# STM32H730_PINOUT.net
KiCad netlist of a schematic drawn in Altium Designer
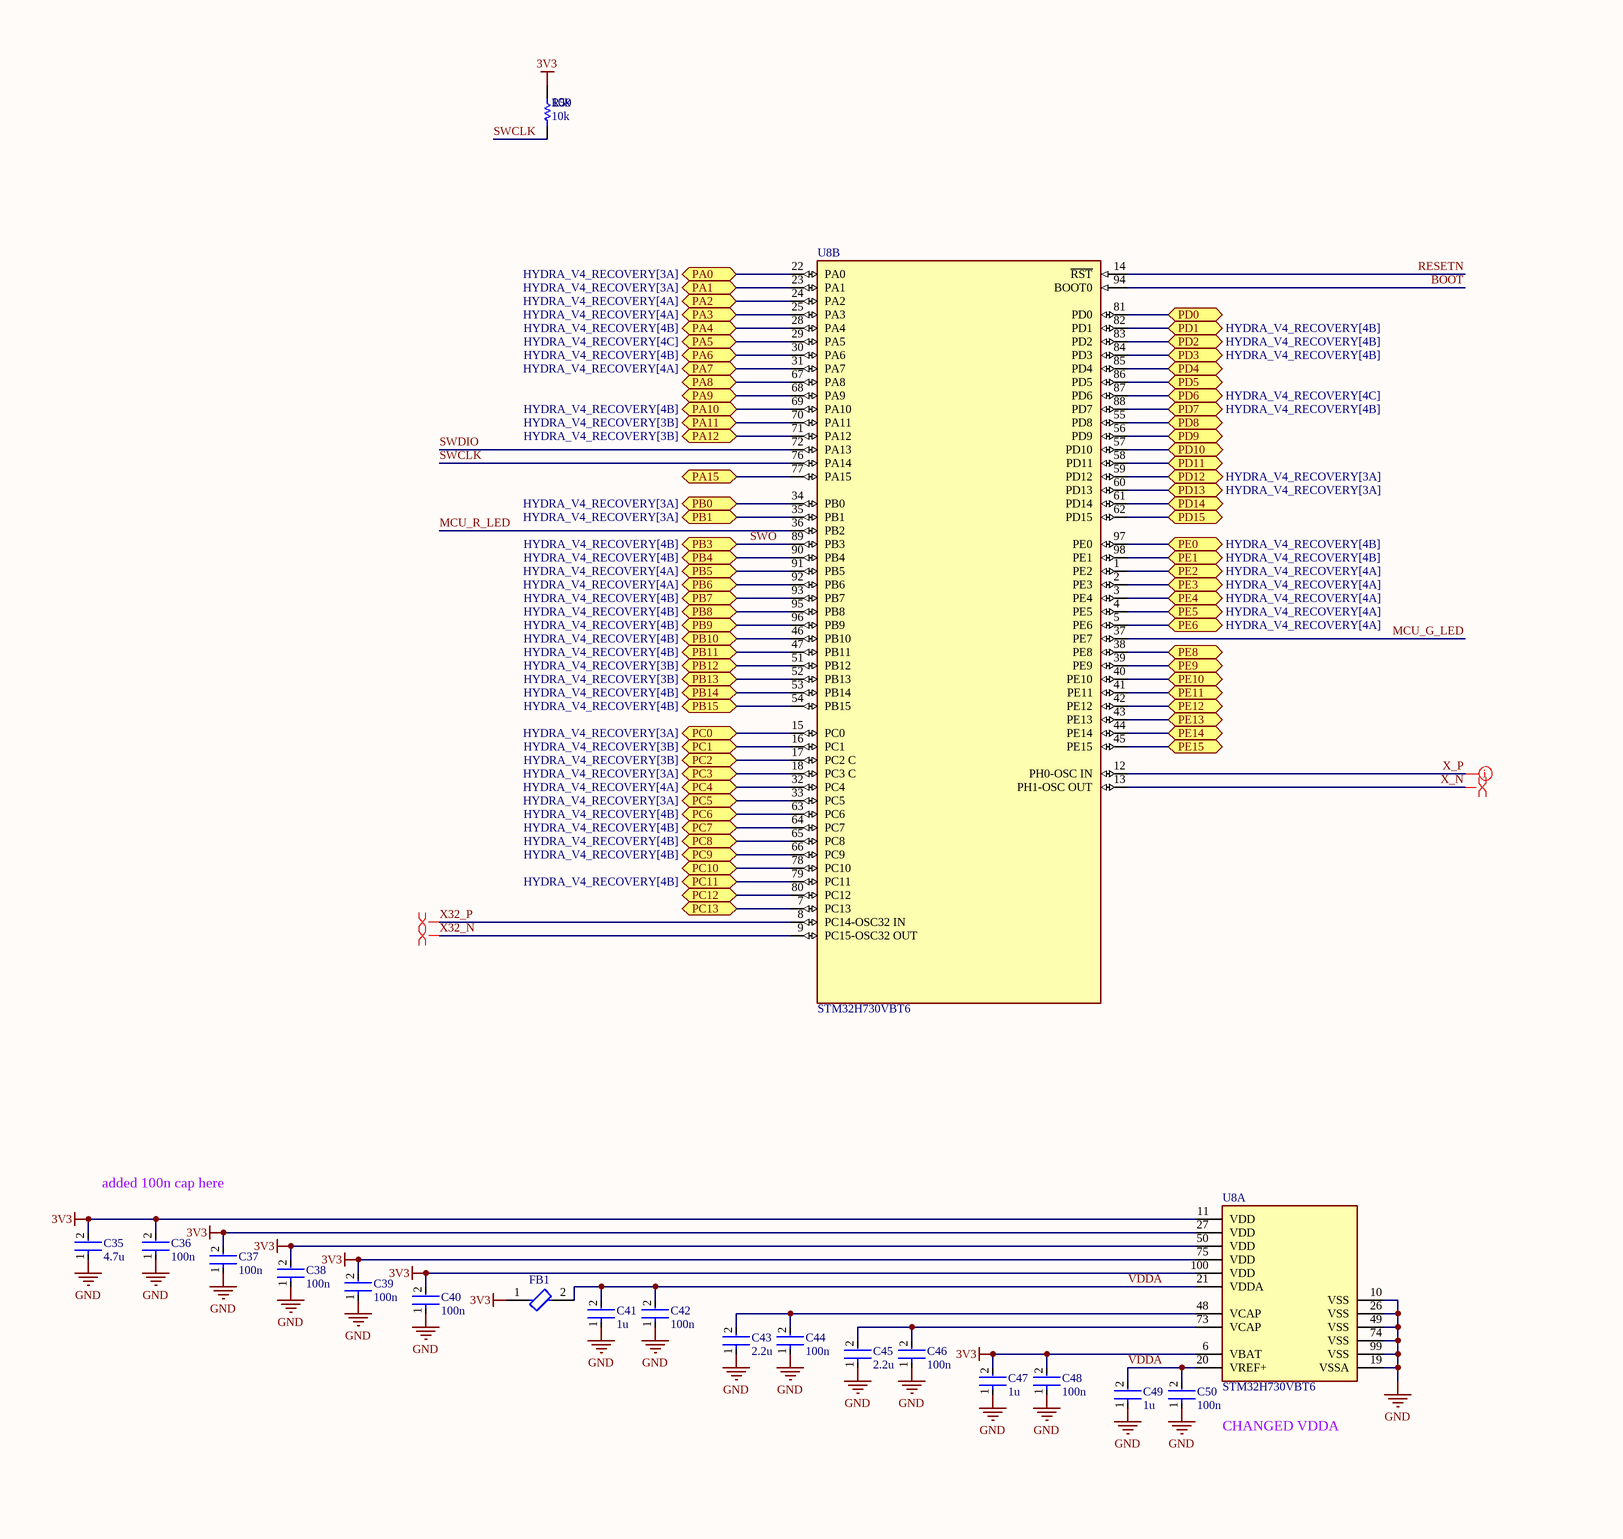
[diagram p0: STM32H730_PINOUT.SchDoc, left]
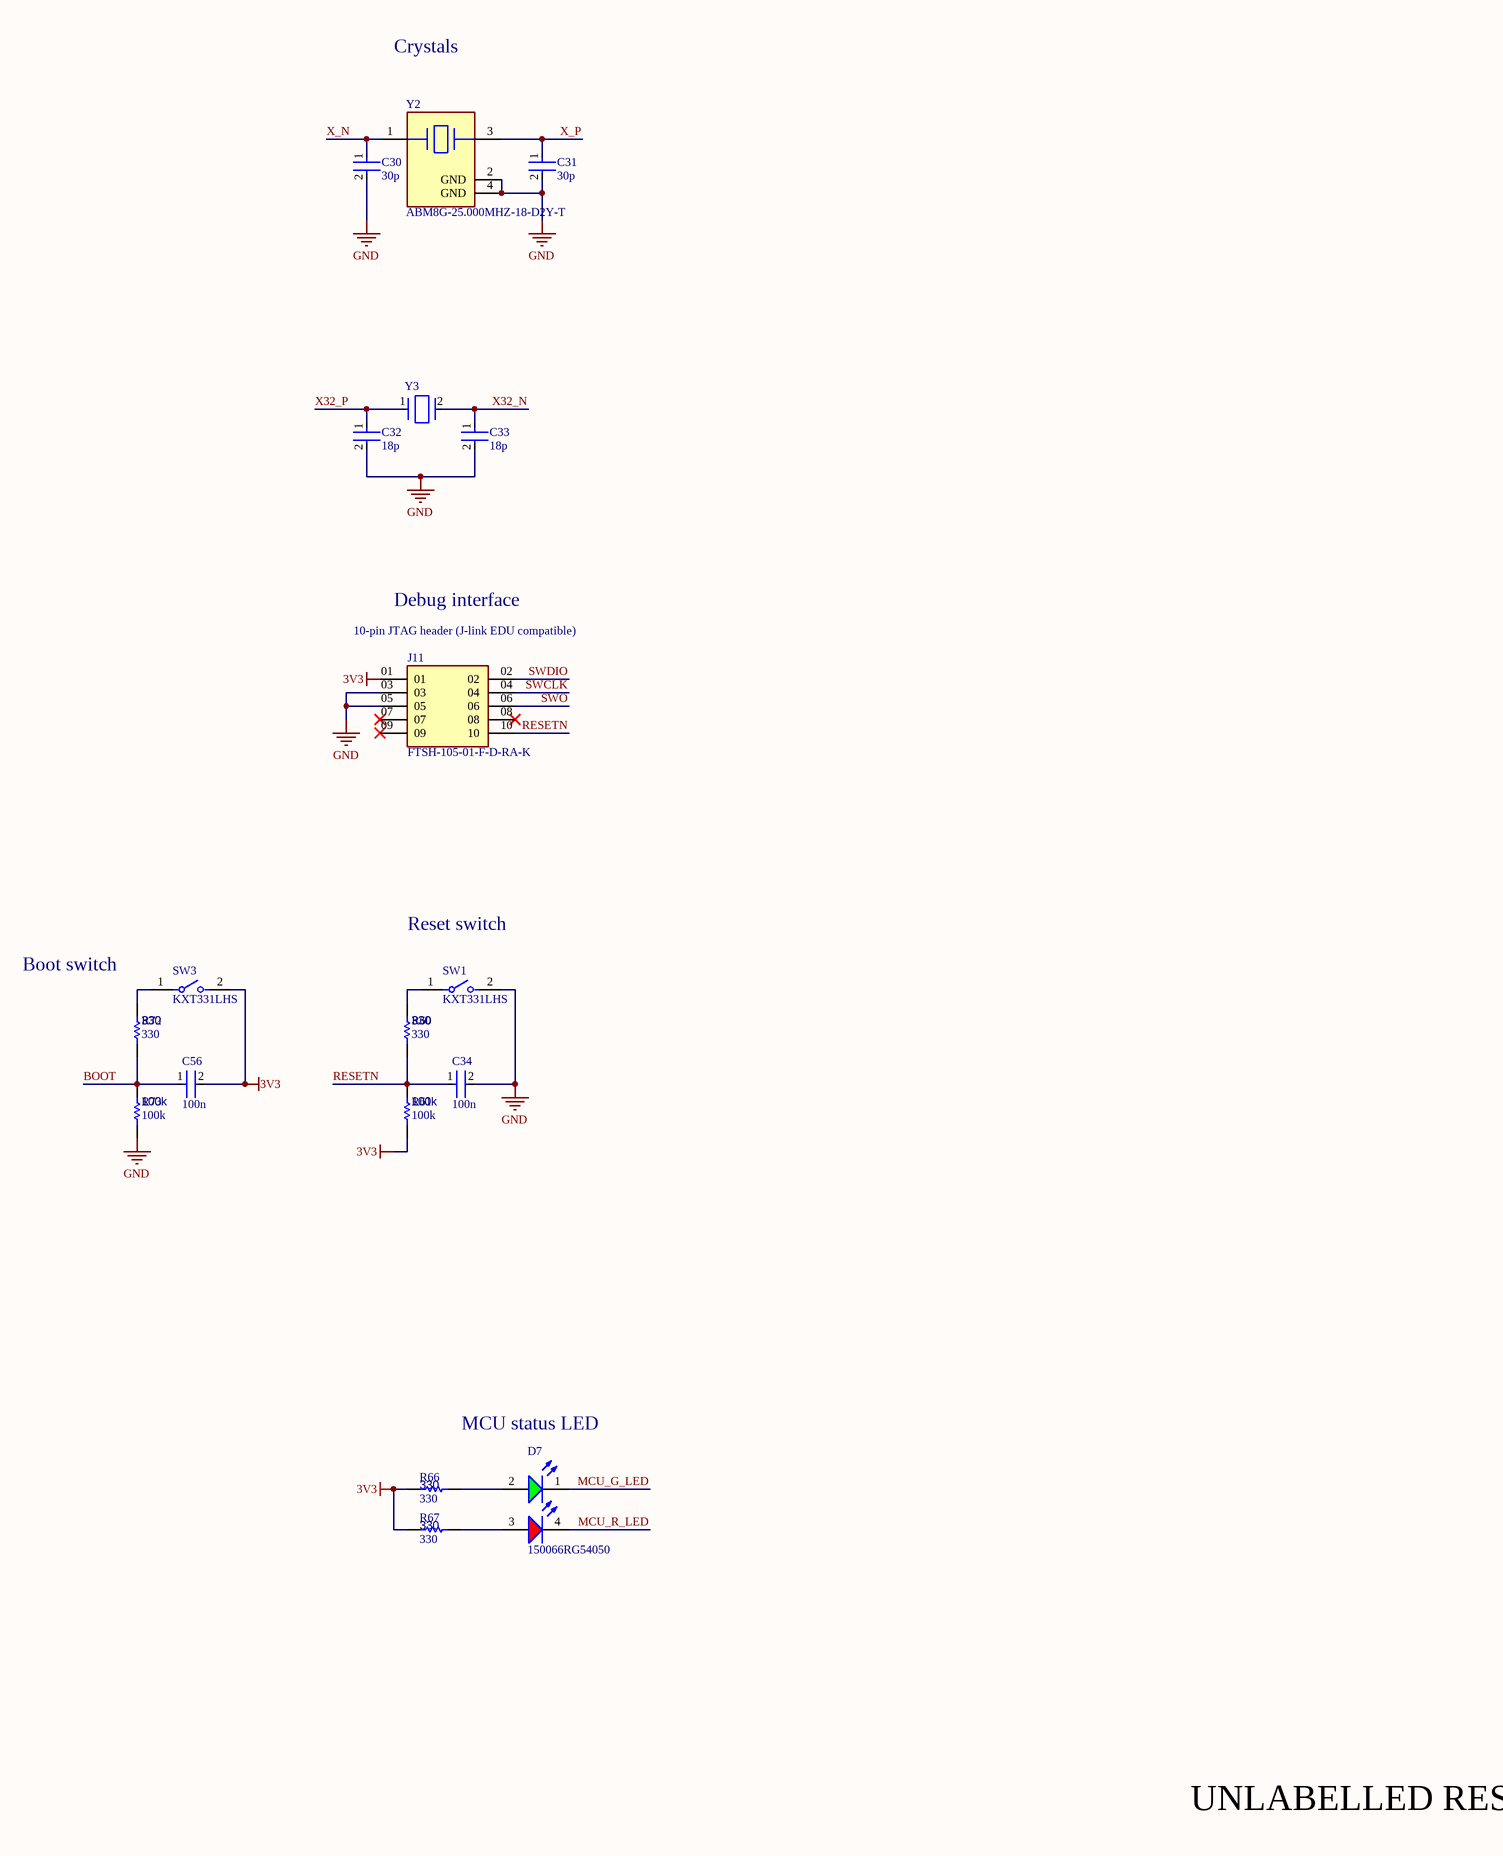
[diagram p1: STM32H730_PINOUT.SchDoc, right]

(export (version "E")
  (design (tool "Eeschema 10.0.6"))
  (components
    (comp (ref "C30")
      (value "30p")
      (footprint "FP-0402-L_1_0_0_05-W_0_5-IPC_A")
      (description "LARGE PADS, 0402 CAP, CHANGE COMMENT TO MATCH REAL P/N")
      (libsource (lib "Space Concordia") (part "b4654b650e69147ec39a6b967a45e02"))
    )
    (comp (ref "C31")
      (value "30p")
      (footprint "FP-0402-L_1_0_0_05-W_0_5-IPC_A")
      (description "LARGE PADS, 0402 CAP, CHANGE COMMENT TO MATCH REAL P/N")
      (libsource (lib "Space Concordia") (part "b4654b650e69147ec39a6b967a45e02"))
    )
    (comp (ref "C32")
      (value "18p")
      (footprint "FP-0402-L_1_0_0_05-W_0_5-IPC_A")
      (description "LARGE PADS, 0402 CAP, CHANGE COMMENT TO MATCH REAL P/N")
      (libsource (lib "Space Concordia") (part "b4654b650e69147ec39a6b967a45e02"))
    )
    (comp (ref "C33")
      (value "18p")
      (footprint "FP-0402-L_1_0_0_05-W_0_5-IPC_A")
      (description "LARGE PADS, 0402 CAP, CHANGE COMMENT TO MATCH REAL P/N")
      (libsource (lib "Space Concordia") (part "b4654b650e69147ec39a6b967a45e02"))
    )
    (comp (ref "C34")
      (value "100n")
      (footprint "FP-0402-L_1_0_0_05-W_0_5-IPC_A")
      (description "LARGE PADS, 0402 CAP, CHANGE COMMENT TO MATCH REAL P/N")
      (libsource (lib "Space Concordia") (part "b4654b650e69147ec39a6b967a45e02"))
    )
    (comp (ref "C35")
      (value "4.7u")
      (footprint "FP-0402-L_1_0_0_05-W_0_5-IPC_A")
      (description "LARGE PADS, 0402 CAP, CHANGE COMMENT TO MATCH REAL P/N")
      (libsource (lib "Space Concordia") (part "b4654b650e69147ec39a6b967a45e02"))
    )
    (comp (ref "C36")
      (value "100n")
      (footprint "FP-0402-L_1_0_0_05-W_0_5-IPC_A")
      (description "LARGE PADS, 0402 CAP, CHANGE COMMENT TO MATCH REAL P/N")
      (libsource (lib "Space Concordia") (part "b4654b650e69147ec39a6b967a45e02"))
    )
    (comp (ref "C37")
      (value "100n")
      (footprint "FP-0402-L_1_0_0_05-W_0_5-IPC_A")
      (description "LARGE PADS, 0402 CAP, CHANGE COMMENT TO MATCH REAL P/N")
      (libsource (lib "Space Concordia") (part "b4654b650e69147ec39a6b967a45e02"))
    )
    (comp (ref "C38")
      (value "100n")
      (footprint "FP-0402-L_1_0_0_05-W_0_5-IPC_A")
      (description "LARGE PADS, 0402 CAP, CHANGE COMMENT TO MATCH REAL P/N")
      (libsource (lib "Space Concordia") (part "b4654b650e69147ec39a6b967a45e02"))
    )
    (comp (ref "C39")
      (value "100n")
      (footprint "FP-0402-L_1_0_0_05-W_0_5-IPC_A")
      (description "LARGE PADS, 0402 CAP, CHANGE COMMENT TO MATCH REAL P/N")
      (libsource (lib "Space Concordia") (part "b4654b650e69147ec39a6b967a45e02"))
    )
    (comp (ref "C40")
      (value "100n")
      (footprint "FP-0402-L_1_0_0_05-W_0_5-IPC_A")
      (description "LARGE PADS, 0402 CAP, CHANGE COMMENT TO MATCH REAL P/N")
      (libsource (lib "Space Concordia") (part "b4654b650e69147ec39a6b967a45e02"))
    )
    (comp (ref "C41")
      (value "1u")
      (footprint "FP-0402-L_1_0_0_05-W_0_5-IPC_A")
      (description "LARGE PADS, 0402 CAP, CHANGE COMMENT TO MATCH REAL P/N")
      (libsource (lib "Space Concordia") (part "b4654b650e69147ec39a6b967a45e02"))
    )
    (comp (ref "C42")
      (value "100n")
      (footprint "FP-0402-L_1_0_0_05-W_0_5-IPC_A")
      (description "LARGE PADS, 0402 CAP, CHANGE COMMENT TO MATCH REAL P/N")
      (libsource (lib "Space Concordia") (part "b4654b650e69147ec39a6b967a45e02"))
    )
    (comp (ref "C43")
      (value "2.2u")
      (footprint "FP-0402-L_1_0_0_05-W_0_5-IPC_A")
      (description "LARGE PADS, 0402 CAP, CHANGE COMMENT TO MATCH REAL P/N")
      (libsource (lib "Space Concordia") (part "b4654b650e69147ec39a6b967a45e02"))
    )
    (comp (ref "C44")
      (value "100n")
      (footprint "FP-0402-L_1_0_0_05-W_0_5-IPC_A")
      (description "LARGE PADS, 0402 CAP, CHANGE COMMENT TO MATCH REAL P/N")
      (libsource (lib "Space Concordia") (part "b4654b650e69147ec39a6b967a45e02"))
    )
    (comp (ref "C45")
      (value "2.2u")
      (footprint "FP-0402-L_1_0_0_05-W_0_5-IPC_A")
      (description "LARGE PADS, 0402 CAP, CHANGE COMMENT TO MATCH REAL P/N")
      (libsource (lib "Space Concordia") (part "b4654b650e69147ec39a6b967a45e02"))
    )
    (comp (ref "C46")
      (value "100n")
      (footprint "FP-0402-L_1_0_0_05-W_0_5-IPC_A")
      (description "LARGE PADS, 0402 CAP, CHANGE COMMENT TO MATCH REAL P/N")
      (libsource (lib "Space Concordia") (part "b4654b650e69147ec39a6b967a45e02"))
    )
    (comp (ref "C47")
      (value "1u")
      (footprint "FP-0402-L_1_0_0_05-W_0_5-IPC_A")
      (description "LARGE PADS, 0402 CAP, CHANGE COMMENT TO MATCH REAL P/N")
      (libsource (lib "Space Concordia") (part "b4654b650e69147ec39a6b967a45e02"))
    )
    (comp (ref "C48")
      (value "100n")
      (footprint "FP-0402-L_1_0_0_05-W_0_5-IPC_A")
      (description "LARGE PADS, 0402 CAP, CHANGE COMMENT TO MATCH REAL P/N")
      (libsource (lib "Space Concordia") (part "b4654b650e69147ec39a6b967a45e02"))
    )
    (comp (ref "C49")
      (value "1u")
      (footprint "FP-0402-L_1_0_0_05-W_0_5-IPC_A")
      (description "LARGE PADS, 0402 CAP, CHANGE COMMENT TO MATCH REAL P/N")
      (libsource (lib "Space Concordia") (part "b4654b650e69147ec39a6b967a45e02"))
    )
    (comp (ref "C50")
      (value "100n")
      (footprint "FP-0402-L_1_0_0_05-W_0_5-IPC_A")
      (description "LARGE PADS, 0402 CAP, CHANGE COMMENT TO MATCH REAL P/N")
      (libsource (lib "Space Concordia") (part "b4654b650e69147ec39a6b967a45e02"))
    )
    (comp (ref "C56")
      (value "100n")
      (footprint "FP-0402-L_1_0_0_05-W_0_5-IPC_A")
      (description "LARGE PADS, 0402 CAP, CHANGE COMMENT TO MATCH REAL P/N")
      (libsource (lib "Space Concordia") (part "b4654b650e69147ec39a6b967a45e02"))
    )
    (comp (ref "D7")
      (value "150066RG54050")
      (footprint "WL-SBCD_0606")
      (description "Led, Red/Grn, 180Mcd/230Mcd, 624Nm/525Nm Rohs Compliant: Yes")
      (fields (field (name "SOURCE") "rgled.SchLib"))
      (libsource (lib "Space Concordia") (part "CMP-004-00034-2"))
    )
    (comp (ref "FB1")
      (value "BLM15PX601SN1D")
      (footprint "FP-BLM15-0_05-MFG")
      (description "Chip Ferrite Bead, 0402, 600Ω @ 100MHz, 0.23Ω, 25%, 900mA")
      (fields (field (name "TOLERANCE") "25%"))
      (libsource (lib "Altium Content Vault") (part "5f30dd21d616792df468990f7003faa"))
    )
    (comp (ref "J11")
      (value "FTSH-105-01-F-D-RA-K")
      (footprint "FTSH-105-01-F-D-RA-K-Footprint-1")
      (libsource (lib "Space Concordia") (part "FTSH-105-01-F-D-RA-K-Symbol-1"))
    )
    (comp (ref "R59")
      (value "10k")
      (footprint "R0603B")
      (description "Resistor")
      (fields (field (name "ALTIUM_VALUE") "10k"))
      (libsource (lib "Space Concordia") (part "Resistor"))
    )
    (comp (ref "R60")
      (value "330")
      (footprint "R0603B")
      (description "Resistor")
      (fields (field (name "ALTIUM_VALUE") "330"))
      (libsource (lib "Space Concordia") (part "Resistor"))
    )
    (comp (ref "R61")
      (value "100k")
      (footprint "R0603B")
      (description "Resistor")
      (fields (field (name "ALTIUM_VALUE") "100k"))
      (libsource (lib "Space Concordia") (part "Resistor"))
    )
    (comp (ref "R66")
      (value "330")
      (footprint "R0603B")
      (description "Resistor")
      (fields (field (name "ALTIUM_VALUE") "330"))
      (libsource (lib "Space Concordia") (part "Resistor"))
    )
    (comp (ref "R67")
      (value "330")
      (footprint "R0603B")
      (description "Resistor")
      (fields (field (name "ALTIUM_VALUE") "330"))
      (libsource (lib "Space Concordia") (part "Resistor"))
    )
    (comp (ref "R72")
      (value "330")
      (footprint "R0603B")
      (description "Resistor")
      (fields (field (name "ALTIUM_VALUE") "330"))
      (libsource (lib "Space Concordia") (part "Resistor"))
    )
    (comp (ref "R73")
      (value "100k")
      (footprint "R0603B")
      (description "Resistor")
      (fields (field (name "ALTIUM_VALUE") "100k"))
      (libsource (lib "Space Concordia") (part "Resistor"))
    )
    (comp (ref "SW1")
      (value "KXT331LHS")
      (footprint "FP-KXT331LHS-MFG")
      (description "SWITCH TACTILE SPST-NO 0.02A 15V")
      (libsource (lib "Altium Content Vault") (part "bb27bde45df87f1f469753f287ef5ae"))
    )
    (comp (ref "SW3")
      (value "KXT331LHS")
      (footprint "FP-KXT331LHS-MFG")
      (description "SWITCH TACTILE SPST-NO 0.02A 15V")
      (libsource (lib "Altium Content Vault") (part "bb27bde45df87f1f469753f287ef5ae"))
    )
    (comp (ref "U8")
      (value "STM32H730VBT6")
      (footprint "FP-LQFP100-1L-IPC_C")
      (description "IC MCU 32BIT 128KB FLASH 100LQFP")
      (libsource (lib "Altium Content Vault") (part "44dc6501260a4d92b846760feb66c20"))
    )
    (comp (ref "Y2")
      (value "ABM8G-25.000MHZ-18-D2Y-T")
      (footprint "FP-ABM8G-MFG")
      (description "Crystal 25MHz ±20ppm (Tol) ±30ppm (Stability) 18pF FUND 60Ω 4-Pin SMD T/R")
      (fields (field (name "TOLERANCE") "20ppm"))
      (libsource (lib "Altium Content Vault") (part "48e526d86b7f2615d98721063c72f49"))
    )
    (comp (ref "Y3")
      (value "ECS-.327-12.5-1210-TR")
      (footprint "FP-ECX-1210-MFG")
      (description "CRYSTAL 32.7680KHZ 12.5PF SMD")
      (fields
        (field (name "OCTOPART") "https://octopart.com/ecs-.327-12.5-1210-tr-ecs+international-81221340")
        (field (name "TOLERANCE") "20ppm")
      )
      (libsource (lib "Altium Content Vault") (part "99724985039315a44fd0d1401b84e49"))
    )
  )
  (nets
    (net (code "1") (name "/BOOT") (class "Default")
      (node (ref "C56") (pin "1") (pinfunction "1_1") (pintype "passive"))
      (node (ref "R72") (pin "2") (pinfunction "2_2") (pintype "passive"))
      (node (ref "R73") (pin "2") (pinfunction "2_2") (pintype "passive"))
      (node (ref "U8") (pin "94") (pinfunction "BOOT0_94") (pintype "input"))
    )
    (net (code "2") (name "/MCU_G_LED") (class "Default")
      (node (ref "D7") (pin "1") (pinfunction "K_1") (pintype "passive"))
      (node (ref "U8") (pin "37") (pinfunction "PE7_37") (pintype "bidirectional"))
    )
    (net (code "3") (name "/MCU_R_LED") (class "Default")
      (node (ref "D7") (pin "4") (pinfunction "K_4") (pintype "passive"))
      (node (ref "U8") (pin "36") (pinfunction "PB2_36") (pintype "bidirectional"))
    )
    (net (code "4") (name "/PA0") (class "Default")
      (node (ref "U8") (pin "22") (pinfunction "PA0_22") (pintype "bidirectional"))
    )
    (net (code "5") (name "/PA1") (class "Default")
      (node (ref "U8") (pin "23") (pinfunction "PA1_23") (pintype "bidirectional"))
    )
    (net (code "6") (name "/PA2") (class "Default")
      (node (ref "U8") (pin "24") (pinfunction "PA2_24") (pintype "bidirectional"))
    )
    (net (code "7") (name "/PA3") (class "Default")
      (node (ref "U8") (pin "25") (pinfunction "PA3_25") (pintype "bidirectional"))
    )
    (net (code "8") (name "/PA4") (class "Default")
      (node (ref "U8") (pin "28") (pinfunction "PA4_28") (pintype "bidirectional"))
    )
    (net (code "9") (name "/PA5") (class "Default")
      (node (ref "U8") (pin "29") (pinfunction "PA5_29") (pintype "bidirectional"))
    )
    (net (code "10") (name "/PA6") (class "Default")
      (node (ref "U8") (pin "30") (pinfunction "PA6_30") (pintype "bidirectional"))
    )
    (net (code "11") (name "/PA7") (class "Default")
      (node (ref "U8") (pin "31") (pinfunction "PA7_31") (pintype "bidirectional"))
    )
    (net (code "12") (name "/PA8") (class "Default")
      (node (ref "U8") (pin "67") (pinfunction "PA8_67") (pintype "bidirectional"))
    )
    (net (code "13") (name "/PA9") (class "Default")
      (node (ref "U8") (pin "68") (pinfunction "PA9_68") (pintype "bidirectional"))
    )
    (net (code "14") (name "/PA10") (class "Default")
      (node (ref "U8") (pin "69") (pinfunction "PA10_69") (pintype "bidirectional"))
    )
    (net (code "15") (name "/PA11") (class "Default")
      (node (ref "U8") (pin "70") (pinfunction "PA11_70") (pintype "bidirectional"))
    )
    (net (code "16") (name "/PA12") (class "Default")
      (node (ref "U8") (pin "71") (pinfunction "PA12_71") (pintype "bidirectional"))
    )
    (net (code "17") (name "/PA15") (class "Default")
      (node (ref "U8") (pin "77") (pinfunction "PA15_77") (pintype "bidirectional"))
    )
    (net (code "18") (name "/PB0") (class "Default")
      (node (ref "U8") (pin "34") (pinfunction "PB0_34") (pintype "bidirectional"))
    )
    (net (code "19") (name "/PB1") (class "Default")
      (node (ref "U8") (pin "35") (pinfunction "PB1_35") (pintype "bidirectional"))
    )
    (net (code "20") (name "/PB4") (class "Default")
      (node (ref "U8") (pin "90") (pinfunction "PB4_90") (pintype "bidirectional"))
    )
    (net (code "21") (name "/PB5") (class "Default")
      (node (ref "U8") (pin "91") (pinfunction "PB5_91") (pintype "bidirectional"))
    )
    (net (code "22") (name "/PB6") (class "Default")
      (node (ref "U8") (pin "92") (pinfunction "PB6_92") (pintype "bidirectional"))
    )
    (net (code "23") (name "/PB7") (class "Default")
      (node (ref "U8") (pin "93") (pinfunction "PB7_93") (pintype "bidirectional"))
    )
    (net (code "24") (name "/PB8") (class "Default")
      (node (ref "U8") (pin "95") (pinfunction "PB8_95") (pintype "bidirectional"))
    )
    (net (code "25") (name "/PB9") (class "Default")
      (node (ref "U8") (pin "96") (pinfunction "PB9_96") (pintype "bidirectional"))
    )
    (net (code "26") (name "/PB10") (class "Default")
      (node (ref "U8") (pin "46") (pinfunction "PB10_46") (pintype "bidirectional"))
    )
    (net (code "27") (name "/PB11") (class "Default")
      (node (ref "U8") (pin "47") (pinfunction "PB11_47") (pintype "bidirectional"))
    )
    (net (code "28") (name "/PB12") (class "Default")
      (node (ref "U8") (pin "51") (pinfunction "PB12_51") (pintype "bidirectional"))
    )
    (net (code "29") (name "/PB13") (class "Default")
      (node (ref "U8") (pin "52") (pinfunction "PB13_52") (pintype "bidirectional"))
    )
    (net (code "30") (name "/PB14") (class "Default")
      (node (ref "U8") (pin "53") (pinfunction "PB14_53") (pintype "bidirectional"))
    )
    (net (code "31") (name "/PB15") (class "Default")
      (node (ref "U8") (pin "54") (pinfunction "PB15_54") (pintype "bidirectional"))
    )
    (net (code "32") (name "/PC0") (class "Default")
      (node (ref "U8") (pin "15") (pinfunction "PC0_15") (pintype "bidirectional"))
    )
    (net (code "33") (name "/PC1") (class "Default")
      (node (ref "U8") (pin "16") (pinfunction "PC1_16") (pintype "bidirectional"))
    )
    (net (code "34") (name "/PC2") (class "Default")
      (node (ref "U8") (pin "17") (pinfunction "PC2_C_17") (pintype "bidirectional"))
    )
    (net (code "35") (name "/PC3") (class "Default")
      (node (ref "U8") (pin "18") (pinfunction "PC3_C_18") (pintype "bidirectional"))
    )
    (net (code "36") (name "/PC4") (class "Default")
      (node (ref "U8") (pin "32") (pinfunction "PC4_32") (pintype "bidirectional"))
    )
    (net (code "37") (name "/PC5") (class "Default")
      (node (ref "U8") (pin "33") (pinfunction "PC5_33") (pintype "bidirectional"))
    )
    (net (code "38") (name "/PC6") (class "Default")
      (node (ref "U8") (pin "63") (pinfunction "PC6_63") (pintype "bidirectional"))
    )
    (net (code "39") (name "/PC7") (class "Default")
      (node (ref "U8") (pin "64") (pinfunction "PC7_64") (pintype "bidirectional"))
    )
    (net (code "40") (name "/PC8") (class "Default")
      (node (ref "U8") (pin "65") (pinfunction "PC8_65") (pintype "bidirectional"))
    )
    (net (code "41") (name "/PC9") (class "Default")
      (node (ref "U8") (pin "66") (pinfunction "PC9_66") (pintype "bidirectional"))
    )
    (net (code "42") (name "/PC10") (class "Default")
      (node (ref "U8") (pin "78") (pinfunction "PC10_78") (pintype "bidirectional"))
    )
    (net (code "43") (name "/PC11") (class "Default")
      (node (ref "U8") (pin "79") (pinfunction "PC11_79") (pintype "bidirectional"))
    )
    (net (code "44") (name "/PC12") (class "Default")
      (node (ref "U8") (pin "80") (pinfunction "PC12_80") (pintype "bidirectional"))
    )
    (net (code "45") (name "/PC13") (class "Default")
      (node (ref "U8") (pin "7") (pinfunction "PC13_7") (pintype "bidirectional"))
    )
    (net (code "46") (name "/PD0") (class "Default")
      (node (ref "U8") (pin "81") (pinfunction "PD0_81") (pintype "bidirectional"))
    )
    (net (code "47") (name "/PD1") (class "Default")
      (node (ref "U8") (pin "82") (pinfunction "PD1_82") (pintype "bidirectional"))
    )
    (net (code "48") (name "/PD2") (class "Default")
      (node (ref "U8") (pin "83") (pinfunction "PD2_83") (pintype "bidirectional"))
    )
    (net (code "49") (name "/PD3") (class "Default")
      (node (ref "U8") (pin "84") (pinfunction "PD3_84") (pintype "bidirectional"))
    )
    (net (code "50") (name "/PD4") (class "Default")
      (node (ref "U8") (pin "85") (pinfunction "PD4_85") (pintype "bidirectional"))
    )
    (net (code "51") (name "/PD5") (class "Default")
      (node (ref "U8") (pin "86") (pinfunction "PD5_86") (pintype "bidirectional"))
    )
    (net (code "52") (name "/PD6") (class "Default")
      (node (ref "U8") (pin "87") (pinfunction "PD6_87") (pintype "bidirectional"))
    )
    (net (code "53") (name "/PD7") (class "Default")
      (node (ref "U8") (pin "88") (pinfunction "PD7_88") (pintype "bidirectional"))
    )
    (net (code "54") (name "/PD8") (class "Default")
      (node (ref "U8") (pin "55") (pinfunction "PD8_55") (pintype "bidirectional"))
    )
    (net (code "55") (name "/PD9") (class "Default")
      (node (ref "U8") (pin "56") (pinfunction "PD9_56") (pintype "bidirectional"))
    )
    (net (code "56") (name "/PD10") (class "Default")
      (node (ref "U8") (pin "57") (pinfunction "PD10_57") (pintype "bidirectional"))
    )
    (net (code "57") (name "/PD11") (class "Default")
      (node (ref "U8") (pin "58") (pinfunction "PD11_58") (pintype "bidirectional"))
    )
    (net (code "58") (name "/PD12") (class "Default")
      (node (ref "U8") (pin "59") (pinfunction "PD12_59") (pintype "bidirectional"))
    )
    (net (code "59") (name "/PD13") (class "Default")
      (node (ref "U8") (pin "60") (pinfunction "PD13_60") (pintype "bidirectional"))
    )
    (net (code "60") (name "/PD14") (class "Default")
      (node (ref "U8") (pin "61") (pinfunction "PD14_61") (pintype "bidirectional"))
    )
    (net (code "61") (name "/PD15") (class "Default")
      (node (ref "U8") (pin "62") (pinfunction "PD15_62") (pintype "bidirectional"))
    )
    (net (code "62") (name "/PE0") (class "Default")
      (node (ref "U8") (pin "97") (pinfunction "PE0_97") (pintype "bidirectional"))
    )
    (net (code "63") (name "/PE1") (class "Default")
      (node (ref "U8") (pin "98") (pinfunction "PE1_98") (pintype "bidirectional"))
    )
    (net (code "64") (name "/PE2") (class "Default")
      (node (ref "U8") (pin "1") (pinfunction "PE2_1") (pintype "bidirectional"))
    )
    (net (code "65") (name "/PE3") (class "Default")
      (node (ref "U8") (pin "2") (pinfunction "PE3_2") (pintype "bidirectional"))
    )
    (net (code "66") (name "/PE4") (class "Default")
      (node (ref "U8") (pin "3") (pinfunction "PE4_3") (pintype "bidirectional"))
    )
    (net (code "67") (name "/PE5") (class "Default")
      (node (ref "U8") (pin "4") (pinfunction "PE5_4") (pintype "bidirectional"))
    )
    (net (code "68") (name "/PE6") (class "Default")
      (node (ref "U8") (pin "5") (pinfunction "PE6_5") (pintype "bidirectional"))
    )
    (net (code "69") (name "/PE8") (class "Default")
      (node (ref "U8") (pin "38") (pinfunction "PE8_38") (pintype "bidirectional"))
    )
    (net (code "70") (name "/PE9") (class "Default")
      (node (ref "U8") (pin "39") (pinfunction "PE9_39") (pintype "bidirectional"))
    )
    (net (code "71") (name "/PE10") (class "Default")
      (node (ref "U8") (pin "40") (pinfunction "PE10_40") (pintype "bidirectional"))
    )
    (net (code "72") (name "/PE11") (class "Default")
      (node (ref "U8") (pin "41") (pinfunction "PE11_41") (pintype "bidirectional"))
    )
    (net (code "73") (name "/PE12") (class "Default")
      (node (ref "U8") (pin "42") (pinfunction "PE12_42") (pintype "bidirectional"))
    )
    (net (code "74") (name "/PE13") (class "Default")
      (node (ref "U8") (pin "43") (pinfunction "PE13_43") (pintype "bidirectional"))
    )
    (net (code "75") (name "/PE14") (class "Default")
      (node (ref "U8") (pin "44") (pinfunction "PE14_44") (pintype "bidirectional"))
    )
    (net (code "76") (name "/PE15") (class "Default")
      (node (ref "U8") (pin "45") (pinfunction "PE15_45") (pintype "bidirectional"))
    )
    (net (code "77") (name "/RESETN") (class "Default")
      (node (ref "C34") (pin "1") (pinfunction "1_1") (pintype "passive"))
      (node (ref "J11") (pin "10") (pinfunction "10_10") (pintype "passive"))
      (node (ref "R60") (pin "1") (pinfunction "1_1") (pintype "passive"))
      (node (ref "R61") (pin "2") (pinfunction "2_2") (pintype "passive"))
      (node (ref "U8") (pin "14") (pinfunction "~{RST}_14") (pintype "input"))
    )
    (net (code "78") (name "/SWCLK") (class "Default")
      (node (ref "J11") (pin "04") (pinfunction "04_04") (pintype "passive"))
      (node (ref "R59") (pin "1") (pinfunction "1_1") (pintype "passive"))
      (node (ref "U8") (pin "76") (pinfunction "PA14_76") (pintype "bidirectional"))
    )
    (net (code "79") (name "/SWDIO") (class "Default")
      (node (ref "J11") (pin "02") (pinfunction "02_02") (pintype "passive"))
      (node (ref "U8") (pin "72") (pinfunction "PA13_72") (pintype "bidirectional"))
    )
    (net (code "80") (name "/SWO") (class "Default")
      (node (ref "J11") (pin "06") (pinfunction "06_06") (pintype "passive"))
      (node (ref "U8") (pin "89") (pinfunction "PB3_89") (pintype "bidirectional"))
    )
    (net (code "81") (name "/VDDA") (class "Default")
      (node (ref "C41") (pin "2") (pinfunction "2_2") (pintype "passive"))
      (node (ref "C42") (pin "2") (pinfunction "2_2") (pintype "passive"))
      (node (ref "C49") (pin "2") (pinfunction "2_2") (pintype "passive"))
      (node (ref "C50") (pin "2") (pinfunction "2_2") (pintype "passive"))
      (node (ref "FB1") (pin "2") (pinfunction "2_2") (pintype "passive"))
      (node (ref "U8") (pin "20") (pinfunction "VREF+_20") (pintype "power_in"))
      (node (ref "U8") (pin "21") (pinfunction "VDDA_21") (pintype "power_in"))
    )
    (net (code "82") (name "/X32_N") (class "Default")
      (node (ref "C33") (pin "1") (pinfunction "1_1") (pintype "passive"))
      (node (ref "U8") (pin "9") (pinfunction "PC15-OSC32_OUT_9") (pintype "bidirectional"))
      (node (ref "Y3") (pin "2") (pinfunction "Out/In_2") (pintype "passive"))
    )
    (net (code "83") (name "/X32_P") (class "Default")
      (node (ref "C32") (pin "1") (pinfunction "1_1") (pintype "passive"))
      (node (ref "U8") (pin "8") (pinfunction "PC14-OSC32_IN_8") (pintype "bidirectional"))
      (node (ref "Y3") (pin "1") (pinfunction "In/Out_1") (pintype "passive"))
    )
    (net (code "84") (name "/X_N") (class "Default")
      (node (ref "C30") (pin "1") (pinfunction "1_1") (pintype "passive"))
      (node (ref "U8") (pin "13") (pinfunction "PH1-OSC_OUT_13") (pintype "bidirectional"))
      (node (ref "Y2") (pin "1") (pinfunction "1_1") (pintype "passive"))
    )
    (net (code "85") (name "/X_P") (class "Default")
      (node (ref "C31") (pin "1") (pinfunction "1_1") (pintype "passive"))
      (node (ref "U8") (pin "12") (pinfunction "PH0-OSC_IN_12") (pintype "bidirectional"))
      (node (ref "Y2") (pin "3") (pinfunction "3_3") (pintype "passive"))
    )
    (net (code "86") (name "3V3") (class "Default")
      (node (ref "C35") (pin "2") (pinfunction "2_2") (pintype "passive"))
      (node (ref "C36") (pin "2") (pinfunction "2_2") (pintype "passive"))
      (node (ref "C37") (pin "2") (pinfunction "2_2") (pintype "passive"))
      (node (ref "C38") (pin "2") (pinfunction "2_2") (pintype "passive"))
      (node (ref "C39") (pin "2") (pinfunction "2_2") (pintype "passive"))
      (node (ref "C40") (pin "2") (pinfunction "2_2") (pintype "passive"))
      (node (ref "C47") (pin "2") (pinfunction "2_2") (pintype "passive"))
      (node (ref "C48") (pin "2") (pinfunction "2_2") (pintype "passive"))
      (node (ref "C56") (pin "2") (pinfunction "2_2") (pintype "passive"))
      (node (ref "FB1") (pin "1") (pinfunction "1_1") (pintype "passive"))
      (node (ref "J11") (pin "01") (pinfunction "01_01") (pintype "passive"))
      (node (ref "R59") (pin "2") (pinfunction "2_2") (pintype "passive"))
      (node (ref "R61") (pin "1") (pinfunction "1_1") (pintype "passive"))
      (node (ref "R66") (pin "2") (pinfunction "2_2") (pintype "passive"))
      (node (ref "R67") (pin "2") (pinfunction "2_2") (pintype "passive"))
      (node (ref "SW3") (pin "2") (pinfunction "2_2") (pintype "passive"))
      (node (ref "U8") (pin "100") (pinfunction "VDD_100") (pintype "power_in"))
      (node (ref "U8") (pin "11") (pinfunction "VDD_11") (pintype "power_in"))
      (node (ref "U8") (pin "27") (pinfunction "VDD_27") (pintype "power_in"))
      (node (ref "U8") (pin "50") (pinfunction "VDD_50") (pintype "power_in"))
      (node (ref "U8") (pin "6") (pinfunction "VBAT_6") (pintype "power_in"))
      (node (ref "U8") (pin "75") (pinfunction "VDD_75") (pintype "power_in"))
    )
    (net (code "87") (name "GND") (class "Default")
      (node (ref "C30") (pin "2") (pinfunction "2_2") (pintype "passive"))
      (node (ref "C31") (pin "2") (pinfunction "2_2") (pintype "passive"))
      (node (ref "C32") (pin "2") (pinfunction "2_2") (pintype "passive"))
      (node (ref "C33") (pin "2") (pinfunction "2_2") (pintype "passive"))
      (node (ref "C34") (pin "2") (pinfunction "2_2") (pintype "passive"))
      (node (ref "C35") (pin "1") (pinfunction "1_1") (pintype "passive"))
      (node (ref "C36") (pin "1") (pinfunction "1_1") (pintype "passive"))
      (node (ref "C37") (pin "1") (pinfunction "1_1") (pintype "passive"))
      (node (ref "C38") (pin "1") (pinfunction "1_1") (pintype "passive"))
      (node (ref "C39") (pin "1") (pinfunction "1_1") (pintype "passive"))
      (node (ref "C40") (pin "1") (pinfunction "1_1") (pintype "passive"))
      (node (ref "C41") (pin "1") (pinfunction "1_1") (pintype "passive"))
      (node (ref "C42") (pin "1") (pinfunction "1_1") (pintype "passive"))
      (node (ref "C43") (pin "1") (pinfunction "1_1") (pintype "passive"))
      (node (ref "C44") (pin "1") (pinfunction "1_1") (pintype "passive"))
      (node (ref "C45") (pin "1") (pinfunction "1_1") (pintype "passive"))
      (node (ref "C46") (pin "1") (pinfunction "1_1") (pintype "passive"))
      (node (ref "C47") (pin "1") (pinfunction "1_1") (pintype "passive"))
      (node (ref "C48") (pin "1") (pinfunction "1_1") (pintype "passive"))
      (node (ref "C49") (pin "1") (pinfunction "1_1") (pintype "passive"))
      (node (ref "C50") (pin "1") (pinfunction "1_1") (pintype "passive"))
      (node (ref "J11") (pin "03") (pinfunction "03_03") (pintype "passive"))
      (node (ref "J11") (pin "05") (pinfunction "05_05") (pintype "passive"))
      (node (ref "R73") (pin "1") (pinfunction "1_1") (pintype "passive"))
      (node (ref "SW1") (pin "2") (pinfunction "2_2") (pintype "passive"))
      (node (ref "U8") (pin "10") (pinfunction "VSS_10") (pintype "power_in"))
      (node (ref "U8") (pin "19") (pinfunction "VSSA_19") (pintype "power_in"))
      (node (ref "U8") (pin "26") (pinfunction "VSS_26") (pintype "power_in"))
      (node (ref "U8") (pin "49") (pinfunction "VSS_49") (pintype "power_in"))
      (node (ref "U8") (pin "74") (pinfunction "VSS_74") (pintype "power_in"))
      (node (ref "U8") (pin "99") (pinfunction "VSS_99") (pintype "power_in"))
      (node (ref "Y2") (pin "2") (pinfunction "GND_2") (pintype "power_in"))
      (node (ref "Y2") (pin "4") (pinfunction "GND_4") (pintype "power_in"))
    )
    (net (code "88") (name "Net-(C43-Pad2)") (class "Default")
      (node (ref "C43") (pin "2") (pinfunction "2_2") (pintype "passive"))
      (node (ref "C44") (pin "2") (pinfunction "2_2") (pintype "passive"))
      (node (ref "U8") (pin "48") (pinfunction "VCAP_48") (pintype "power_in"))
    )
    (net (code "89") (name "Net-(C45-Pad2)") (class "Default")
      (node (ref "C45") (pin "2") (pinfunction "2_2") (pintype "passive"))
      (node (ref "C46") (pin "2") (pinfunction "2_2") (pintype "passive"))
      (node (ref "U8") (pin "73") (pinfunction "VCAP_73") (pintype "power_in"))
    )
    (net (code "90") (name "Net-(D7-A-Pad2)") (class "Default")
      (node (ref "D7") (pin "2") (pinfunction "A_2") (pintype "passive"))
      (node (ref "R66") (pin "1") (pinfunction "1_1") (pintype "passive"))
    )
    (net (code "91") (name "Net-(D7-A-Pad3)") (class "Default")
      (node (ref "D7") (pin "3") (pinfunction "A_3") (pintype "passive"))
      (node (ref "R67") (pin "1") (pinfunction "1_1") (pintype "passive"))
    )
    (net (code "92") (name "Net-(R60-Pad2)") (class "Default")
      (node (ref "R60") (pin "2") (pinfunction "2_2") (pintype "passive"))
      (node (ref "SW1") (pin "1") (pinfunction "1_1") (pintype "passive"))
    )
    (net (code "93") (name "Net-(R72-Pad1)") (class "Default")
      (node (ref "R72") (pin "1") (pinfunction "1_1") (pintype "passive"))
      (node (ref "SW3") (pin "1") (pinfunction "1_1") (pintype "passive"))
    )
    (net (code "94") (name "unconnected-(J11-Pad07)") (class "Default")
      (node (ref "J11") (pin "07") (pinfunction "07_07") (pintype "passive+no_connect"))
    )
    (net (code "95") (name "unconnected-(J11-Pad08)") (class "Default")
      (node (ref "J11") (pin "08") (pinfunction "08_08") (pintype "passive+no_connect"))
    )
    (net (code "96") (name "unconnected-(J11-Pad09)") (class "Default")
      (node (ref "J11") (pin "09") (pinfunction "09_09") (pintype "passive+no_connect"))
    )
  )
)
